# Buildplate_v1_0.net
KiCad netlist of a schematic drawn in EAGLE
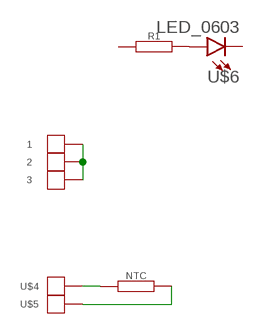
[diagram p0: schematic, sheet 1]

(export (version "E")
  (design (tool "Eeschema 10.0.6"))
  (components
    (comp (ref "1")
      (value "PAD_POGOPIN_1.3MM")
      (footprint "eagle-import:PAD_POGOPIN_1.3MM")
      (libsource (lib "eagle-import") (part "PAD_POGOPIN_1.3MM"))
    )
    (comp (ref "2")
      (value "PAD_POGOPIN_1.3MM")
      (footprint "eagle-import:PAD_POGOPIN_1.3MM")
      (libsource (lib "eagle-import") (part "PAD_POGOPIN_1.3MM"))
    )
    (comp (ref "3")
      (value "PAD_POGOPIN_1.3MM")
      (footprint "eagle-import:PAD_POGOPIN_1.3MM")
      (libsource (lib "eagle-import") (part "PAD_POGOPIN_1.3MM"))
    )
    (comp (ref "NTC")
      (value "RESISTOR0603-RES")
      (footprint "eagle-import:0603-RES")
      (libsource (lib "eagle-import") (part "RESISTOR0603-RES"))
    )
    (comp (ref "R1")
      (value "RESISTOR0603-RES")
      (footprint "eagle-import:0603-RES")
      (libsource (lib "eagle-import") (part "RESISTOR0603-RES"))
    )
    (comp (ref "U$4")
      (value "PAD_50X100MIL")
      (footprint "eagle-import:PAD_50X100MIL")
      (libsource (lib "eagle-import") (part "PAD_50X100MIL"))
    )
    (comp (ref "U$5")
      (value "PAD_50X100MIL")
      (footprint "eagle-import:PAD_50X100MIL")
      (libsource (lib "eagle-import") (part "PAD_50X100MIL"))
    )
    (comp (ref "U$6")
      (value "LED_0603")
      (footprint "eagle-import:0603")
      (libsource (lib "eagle-import") (part "LED_0603"))
    )
  )
  (nets
    (net (code "1") (name "Net-(1-PadP$1)") (class "Default")
      (node (ref "1") (pin "P$1") (pinfunction "P$1_P$1") (pintype "bidirectional"))
      (node (ref "2") (pin "P$1") (pinfunction "P$1_P$1") (pintype "bidirectional"))
      (node (ref "3") (pin "P$1") (pinfunction "P$1_P$1") (pintype "bidirectional"))
    )
    (net (code "2") (name "Net-(NTC-Pad1)") (class "Default")
      (node (ref "NTC") (pin "1") (pinfunction "1_1") (pintype "passive"))
      (node (ref "U$4") (pin "P$1") (pinfunction "P$1_P$1") (pintype "bidirectional"))
    )
    (net (code "3") (name "Net-(NTC-Pad2)") (class "Default")
      (node (ref "NTC") (pin "2") (pinfunction "2_2") (pintype "passive"))
      (node (ref "U$5") (pin "P$1") (pinfunction "P$1_P$1") (pintype "bidirectional"))
    )
    (net (code "4") (name "Net-(R1-Pad2)") (class "Default")
      (node (ref "R1") (pin "2") (pinfunction "2_2") (pintype "passive"))
      (node (ref "U$6") (pin "A") (pinfunction "A_A") (pintype "passive"))
    )
    (net (code "5") (name "unconnected-(R1-Pad1)") (class "Default")
      (node (ref "R1") (pin "1") (pinfunction "1_1") (pintype "passive"))
    )
    (net (code "6") (name "unconnected-(U$6-PadC)") (class "Default")
      (node (ref "U$6") (pin "C") (pinfunction "C_C") (pintype "passive"))
    )
  )
)
